# power_NAND.net
KiCad netlist of a schematic drawn in EAGLE
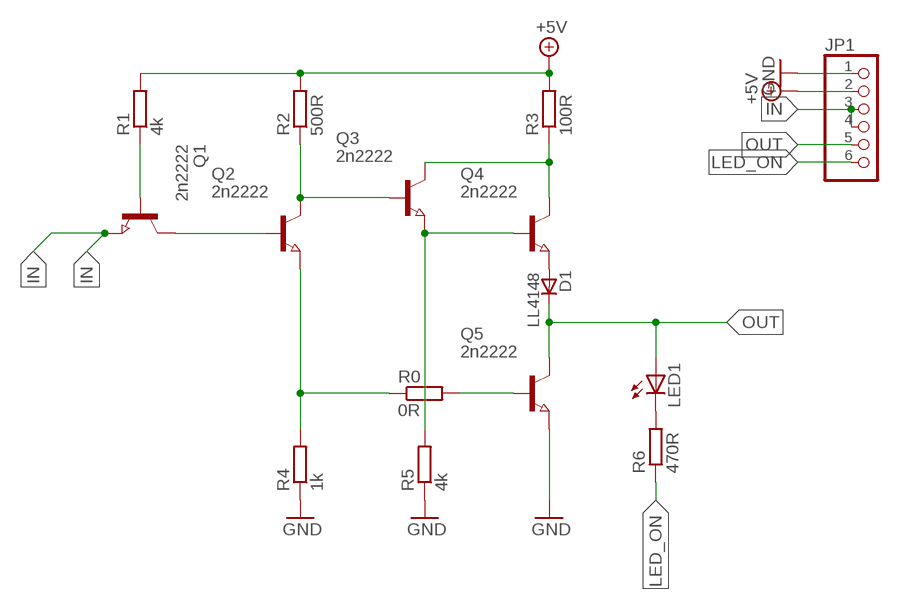
[diagram p0: schematic, sheet 1]

(export (version "E")
  (design (tool "Eeschema 10.0.6"))
  (components
    (comp (ref "D1")
      (value "LL4148")
      (footprint "eagle-import:SOD80_DO213AA_MINIMELF")
      (libsource (lib "eagle-import") (part "LL4148"))
    )
    (comp (ref "JP1")
      (value "PINHD-1X06_2.54-SMD-90°")
      (footprint "eagle-import:1X06SMD_90")
      (libsource (lib "eagle-import") (part "PINHD-1X06_2.54-SMD-90°"))
    )
    (comp (ref "LED1")
      (value "LEDCHIPLED_0805")
      (footprint "eagle-import:CHIPLED_0805")
      (libsource (lib "eagle-import") (part "LEDCHIPLED_0805"))
    )
    (comp (ref "Q1")
      (value "2n2222")
      (footprint "eagle-import:SOT23")
      (libsource (lib "eagle-import") (part "NPN-TRANSISTOR_SOT23"))
    )
    (comp (ref "Q2")
      (value "2n2222")
      (footprint "eagle-import:SOT23")
      (libsource (lib "eagle-import") (part "NPN-TRANSISTOR_SOT23"))
    )
    (comp (ref "Q3")
      (value "2n2222")
      (footprint "eagle-import:SOT23")
      (libsource (lib "eagle-import") (part "NPN-TRANSISTOR_SOT23"))
    )
    (comp (ref "Q4")
      (value "2n2222")
      (footprint "eagle-import:SOT23")
      (libsource (lib "eagle-import") (part "NPN-TRANSISTOR_SOT23"))
    )
    (comp (ref "Q5")
      (value "2n2222")
      (footprint "eagle-import:SOT23")
      (libsource (lib "eagle-import") (part "NPN-TRANSISTOR_SOT23"))
    )
    (comp (ref "R0")
      (value "0R")
      (footprint "eagle-import:R1206")
      (libsource (lib "eagle-import") (part "R-EU_R1206"))
    )
    (comp (ref "R1")
      (value "4k")
      (footprint "eagle-import:R0805")
      (libsource (lib "eagle-import") (part "R-EU_R0805"))
    )
    (comp (ref "R2")
      (value "500R")
      (footprint "eagle-import:R0805")
      (libsource (lib "eagle-import") (part "R-EU_R0805"))
    )
    (comp (ref "R3")
      (value "100R")
      (footprint "eagle-import:R0805")
      (libsource (lib "eagle-import") (part "R-EU_R0805"))
    )
    (comp (ref "R4")
      (value "1k")
      (footprint "eagle-import:R0805")
      (libsource (lib "eagle-import") (part "R-EU_R0805"))
    )
    (comp (ref "R5")
      (value "4k")
      (footprint "eagle-import:R0805")
      (libsource (lib "eagle-import") (part "R-EU_R0805"))
    )
    (comp (ref "R6")
      (value "470R")
      (footprint "eagle-import:R0805")
      (libsource (lib "eagle-import") (part "R-EU_R0805"))
    )
  )
  (nets
    (net (code "1") (name "+5V") (class "Default")
      (node (ref "JP1") (pin "2") (pinfunction "2_2") (pintype "passive"))
      (node (ref "R1") (pin "2") (pinfunction "2_2") (pintype "passive"))
      (node (ref "R2") (pin "2") (pinfunction "2_2") (pintype "passive"))
      (node (ref "R3") (pin "2") (pinfunction "2_2") (pintype "passive"))
    )
    (net (code "2") (name "GND") (class "Default")
      (node (ref "JP1") (pin "1") (pinfunction "1_1") (pintype "passive"))
      (node (ref "Q5") (pin "2") (pinfunction "E_2") (pintype "passive"))
      (node (ref "R4") (pin "1") (pinfunction "1_1") (pintype "passive"))
      (node (ref "R5") (pin "1") (pinfunction "1_1") (pintype "passive"))
    )
    (net (code "3") (name "IN") (class "Default")
      (node (ref "JP1") (pin "3") (pinfunction "3_3") (pintype "passive"))
      (node (ref "JP1") (pin "4") (pinfunction "4_4") (pintype "passive"))
      (node (ref "Q1") (pin "2") (pinfunction "E_2") (pintype "passive"))
    )
    (net (code "4") (name "LED_ON") (class "Default")
      (node (ref "JP1") (pin "6") (pinfunction "6_6") (pintype "passive"))
      (node (ref "R6") (pin "1") (pinfunction "1_1") (pintype "passive"))
    )
    (net (code "5") (name "Net-(LED1-PadC)") (class "Default")
      (node (ref "LED1") (pin "C") (pinfunction "C_C") (pintype "passive"))
      (node (ref "R6") (pin "2") (pinfunction "2_2") (pintype "passive"))
    )
    (net (code "6") (name "Net-(Q1-B)") (class "Default")
      (node (ref "Q1") (pin "1") (pinfunction "B_1") (pintype "passive"))
      (node (ref "R1") (pin "1") (pinfunction "1_1") (pintype "passive"))
    )
    (net (code "7") (name "Net-(Q1-C)") (class "Default")
      (node (ref "Q1") (pin "3") (pinfunction "C_3") (pintype "passive"))
      (node (ref "Q2") (pin "1") (pinfunction "B_1") (pintype "passive"))
    )
    (net (code "8") (name "Net-(Q2-C)") (class "Default")
      (node (ref "Q2") (pin "3") (pinfunction "C_3") (pintype "passive"))
      (node (ref "Q3") (pin "1") (pinfunction "B_1") (pintype "passive"))
      (node (ref "R2") (pin "1") (pinfunction "1_1") (pintype "passive"))
    )
    (net (code "9") (name "Net-(Q2-E)") (class "Default")
      (node (ref "Q2") (pin "2") (pinfunction "E_2") (pintype "passive"))
      (node (ref "R0") (pin "1") (pinfunction "1_1") (pintype "passive"))
      (node (ref "R4") (pin "2") (pinfunction "2_2") (pintype "passive"))
    )
    (net (code "10") (name "Net-(Q3-C)") (class "Default")
      (node (ref "Q3") (pin "3") (pinfunction "C_3") (pintype "passive"))
      (node (ref "Q4") (pin "3") (pinfunction "C_3") (pintype "passive"))
      (node (ref "R3") (pin "1") (pinfunction "1_1") (pintype "passive"))
    )
    (net (code "11") (name "Net-(Q3-E)") (class "Default")
      (node (ref "Q3") (pin "2") (pinfunction "E_2") (pintype "passive"))
      (node (ref "Q4") (pin "1") (pinfunction "B_1") (pintype "passive"))
      (node (ref "R5") (pin "2") (pinfunction "2_2") (pintype "passive"))
    )
    (net (code "12") (name "Net-(Q4-E)") (class "Default")
      (node (ref "D1") (pin "A") (pinfunction "A_A") (pintype "passive"))
      (node (ref "Q4") (pin "2") (pinfunction "E_2") (pintype "passive"))
    )
    (net (code "13") (name "Net-(Q5-B)") (class "Default")
      (node (ref "Q5") (pin "1") (pinfunction "B_1") (pintype "passive"))
      (node (ref "R0") (pin "2") (pinfunction "2_2") (pintype "passive"))
    )
    (net (code "14") (name "OUT") (class "Default")
      (node (ref "D1") (pin "C") (pinfunction "C_C") (pintype "passive"))
      (node (ref "JP1") (pin "5") (pinfunction "5_5") (pintype "passive"))
      (node (ref "LED1") (pin "A") (pinfunction "A_A") (pintype "passive"))
      (node (ref "Q5") (pin "3") (pinfunction "C_3") (pintype "passive"))
    )
  )
)
